# NodeMCU_AC_Switch.net
KiCad netlist of a schematic drawn in EAGLE
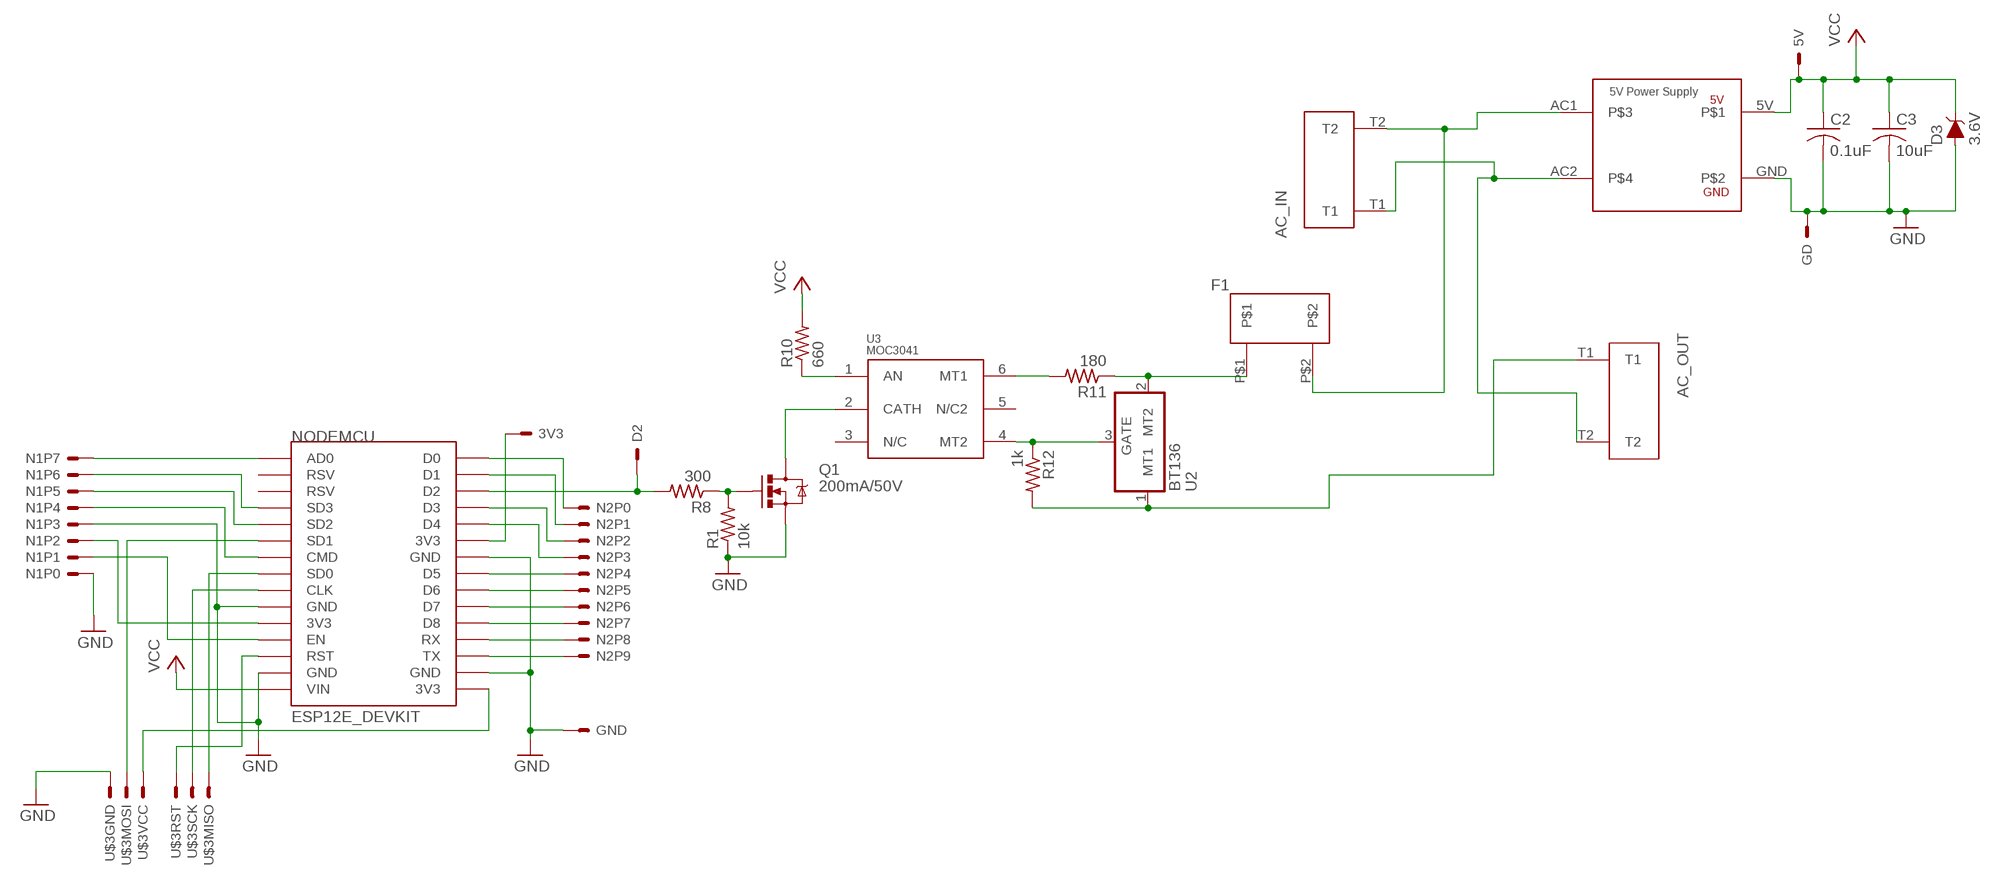
[diagram p0: schematic, sheet 1]

(export (version "E")
  (design (tool "Eeschema 10.0.6"))
  (components
    (comp (ref "3V3")
      (value "1PINHEADER_S")
      (footprint "eagle-import:1PINHEADER_S")
      (libsource (lib "eagle-import") (part "1PINHEADER_S"))
    )
    (comp (ref "5V")
      (value "1PINHEADER_S")
      (footprint "eagle-import:1PINHEADER_S")
      (libsource (lib "eagle-import") (part "1PINHEADER_S"))
    )
    (comp (ref "AC_IN")
      (value "2PIN_SCREW_TERM")
      (footprint "eagle-import:2PIN_SCREW_TERM")
      (libsource (lib "eagle-import") (part "2PIN_SCREW_TERM"))
    )
    (comp (ref "AC_OUT")
      (value "2PIN_SCREW_TERM")
      (footprint "eagle-import:2PIN_SCREW_TERM")
      (libsource (lib "eagle-import") (part "2PIN_SCREW_TERM"))
    )
    (comp (ref "C2")
      (value "0.1uF")
      (footprint "eagle-import:C1206")
      (libsource (lib "eagle-import") (part "C-USC1206"))
    )
    (comp (ref "C3")
      (value "10uF")
      (footprint "eagle-import:C1206")
      (libsource (lib "eagle-import") (part "C-USC1206"))
    )
    (comp (ref "D2")
      (value "1PINHEADER_S")
      (footprint "eagle-import:1PINHEADER_S")
      (libsource (lib "eagle-import") (part "1PINHEADER_S"))
    )
    (comp (ref "D3")
      (value "3.6V")
      (footprint "eagle-import:SOD-323")
      (libsource (lib "eagle-import") (part "DIODE-ZENER-BZT52C3V6S"))
    )
    (comp (ref "F1")
      (value "FUSE_HOLDER")
      (footprint "eagle-import:FUSE_HOLDER")
      (libsource (lib "eagle-import") (part "FUSE_HOLDER"))
    )
    (comp (ref "GD")
      (value "1PINHEADER_S")
      (footprint "eagle-import:1PINHEADER_S")
      (libsource (lib "eagle-import") (part "1PINHEADER_S"))
    )
    (comp (ref "GND")
      (value "1PINHEADER_S")
      (footprint "eagle-import:1PINHEADER_S")
      (libsource (lib "eagle-import") (part "1PINHEADER_S"))
    )
    (comp (ref "N1")
      (value "8PINHEADER")
      (footprint "eagle-import:8PINHEADER")
      (libsource (lib "eagle-import") (part "8PINHEADER"))
    )
    (comp (ref "N2")
      (value "10PINHEADER")
      (footprint "eagle-import:10PINHEADER")
      (libsource (lib "eagle-import") (part "10PINHEADER"))
    )
    (comp (ref "NODEMCU")
      (value "ESP12E_DEVKIT")
      (footprint "eagle-import:ESP12E_DEVKIT")
      (libsource (lib "eagle-import") (part "ESP12E_DEVKIT"))
    )
    (comp (ref "Q1")
      (value "200mA/50V")
      (footprint "eagle-import:SOT23-3")
      (libsource (lib "eagle-import") (part "MOSFET-NCHANNELBSS138"))
    )
    (comp (ref "R1")
      (value "10k")
      (footprint "eagle-import:R1206")
      (libsource (lib "eagle-import") (part "R-US_R1206"))
    )
    (comp (ref "R8")
      (value "300")
      (footprint "eagle-import:R1206")
      (libsource (lib "eagle-import") (part "R-US_R1206"))
    )
    (comp (ref "R10")
      (value "660")
      (footprint "eagle-import:R1206")
      (libsource (lib "eagle-import") (part "R-US_R1206"))
    )
    (comp (ref "R11")
      (value "180")
      (footprint "eagle-import:R1206")
      (libsource (lib "eagle-import") (part "R-US_R1206"))
    )
    (comp (ref "R12")
      (value "1k")
      (footprint "eagle-import:R1206")
      (libsource (lib "eagle-import") (part "R-US_R1206"))
    )
    (comp (ref "U$2")
      (value "5V_POWER_SUPPLY")
      (footprint "eagle-import:5V_POWER_SUPPLY")
      (libsource (lib "eagle-import") (part "5V_POWER_SUPPLY"))
    )
    (comp (ref "U$3")
      (value "2X3_HEADER")
      (footprint "eagle-import:2X3_HEADER")
      (libsource (lib "eagle-import") (part "2X3_HEADER"))
    )
    (comp (ref "U2")
      (value "BT136")
      (footprint "eagle-import:BT136")
      (libsource (lib "eagle-import") (part "BT136"))
    )
    (comp (ref "U3")
      (value "MOC3041")
      (footprint "eagle-import:MOC3041")
      (libsource (lib "eagle-import") (part "MOC3041"))
    )
  )
  (nets
    (net (code "1") (name "GND") (class "Default")
      (node (ref "C2") (pin "2") (pinfunction "2_2") (pintype "passive"))
      (node (ref "C3") (pin "2") (pinfunction "2_2") (pintype "passive"))
      (node (ref "D3") (pin "A") (pinfunction "A_A") (pintype "passive"))
      (node (ref "GD") (pin "P$1") (pinfunction "S_P$1") (pintype "passive"))
      (node (ref "GND") (pin "P$1") (pinfunction "S_P$1") (pintype "passive"))
      (node (ref "N1") (pin "P0") (pinfunction "S_P0") (pintype "passive"))
      (node (ref "N1") (pin "P3") (pinfunction "S_P3") (pintype "passive"))
      (node (ref "NODEMCU") (pin "GND@0") (pinfunction "GND_GND@0") (pintype "bidirectional"))
      (node (ref "NODEMCU") (pin "GND@1") (pinfunction "GND_GND@1") (pintype "bidirectional"))
      (node (ref "NODEMCU") (pin "GND@2") (pinfunction "GND_GND@2") (pintype "bidirectional"))
      (node (ref "NODEMCU") (pin "GND@3") (pinfunction "GND_GND@3") (pintype "bidirectional"))
      (node (ref "Q1") (pin "2") (pinfunction "S_2") (pintype "passive"))
      (node (ref "R1") (pin "1") (pinfunction "1_1") (pintype "passive"))
      (node (ref "U$2") (pin "GND") (pinfunction "P$2_GND") (pintype "bidirectional"))
      (node (ref "U$3") (pin "GND") (pinfunction "S_GND") (pintype "passive"))
    )
    (net (code "2") (name "Net-(3V3-S)") (class "Default")
      (node (ref "3V3") (pin "P$1") (pinfunction "S_P$1") (pintype "passive"))
      (node (ref "NODEMCU") (pin "3V3@1") (pinfunction "3V3_3V3@1") (pintype "bidirectional"))
    )
    (net (code "3") (name "Net-(D2-S)") (class "Default")
      (node (ref "D2") (pin "P$1") (pinfunction "S_P$1") (pintype "passive"))
      (node (ref "NODEMCU") (pin "D2") (pinfunction "D2_D2") (pintype "bidirectional"))
      (node (ref "R8") (pin "2") (pinfunction "2_2") (pintype "passive"))
    )
    (net (code "4") (name "Net-(N1B-S)") (class "Default")
      (node (ref "N1") (pin "P1") (pinfunction "S_P1") (pintype "passive"))
      (node (ref "NODEMCU") (pin "EN") (pinfunction "EN_EN") (pintype "bidirectional"))
    )
    (net (code "5") (name "Net-(N1C-S)") (class "Default")
      (node (ref "N1") (pin "P2") (pinfunction "S_P2") (pintype "passive"))
      (node (ref "NODEMCU") (pin "3V3@0") (pinfunction "3V3_3V3@0") (pintype "bidirectional"))
    )
    (net (code "6") (name "Net-(N1E-S)") (class "Default")
      (node (ref "N1") (pin "P4") (pinfunction "S_P4") (pintype "passive"))
      (node (ref "NODEMCU") (pin "CMD") (pinfunction "CMD_CMD") (pintype "bidirectional"))
    )
    (net (code "7") (name "Net-(N1F-S)") (class "Default")
      (node (ref "N1") (pin "P5") (pinfunction "S_P5") (pintype "passive"))
      (node (ref "NODEMCU") (pin "SD2") (pinfunction "SD2_SD2") (pintype "bidirectional"))
    )
    (net (code "8") (name "Net-(N1G-S)") (class "Default")
      (node (ref "N1") (pin "P6") (pinfunction "S_P6") (pintype "passive"))
      (node (ref "NODEMCU") (pin "SD3") (pinfunction "SD3_SD3") (pintype "bidirectional"))
    )
    (net (code "9") (name "Net-(N1H-S)") (class "Default")
      (node (ref "N1") (pin "P7") (pinfunction "S_P7") (pintype "passive"))
      (node (ref "NODEMCU") (pin "AD0") (pinfunction "AD0_AD0") (pintype "bidirectional"))
    )
    (net (code "10") (name "Net-(N2A-S)") (class "Default")
      (node (ref "N2") (pin "P0") (pinfunction "S_P0") (pintype "passive"))
      (node (ref "NODEMCU") (pin "D0") (pinfunction "D0_D0") (pintype "bidirectional"))
    )
    (net (code "11") (name "Net-(N2B-S)") (class "Default")
      (node (ref "N2") (pin "P1") (pinfunction "S_P1") (pintype "passive"))
      (node (ref "NODEMCU") (pin "D1") (pinfunction "D1_D1") (pintype "bidirectional"))
    )
    (net (code "12") (name "Net-(N2C-S)") (class "Default")
      (node (ref "N2") (pin "P2") (pinfunction "S_P2") (pintype "passive"))
      (node (ref "NODEMCU") (pin "D3") (pinfunction "D3_D3") (pintype "bidirectional"))
    )
    (net (code "13") (name "Net-(N2D-S)") (class "Default")
      (node (ref "N2") (pin "P3") (pinfunction "S_P3") (pintype "passive"))
      (node (ref "NODEMCU") (pin "D4") (pinfunction "D4_D4") (pintype "bidirectional"))
    )
    (net (code "14") (name "Net-(N2E-S)") (class "Default")
      (node (ref "N2") (pin "P4") (pinfunction "S_P4") (pintype "passive"))
      (node (ref "NODEMCU") (pin "D5") (pinfunction "D5_D5") (pintype "bidirectional"))
    )
    (net (code "15") (name "Net-(N2F-S)") (class "Default")
      (node (ref "N2") (pin "P5") (pinfunction "S_P5") (pintype "passive"))
      (node (ref "NODEMCU") (pin "D6") (pinfunction "D6_D6") (pintype "bidirectional"))
    )
    (net (code "16") (name "Net-(N2G-S)") (class "Default")
      (node (ref "N2") (pin "P6") (pinfunction "S_P6") (pintype "passive"))
      (node (ref "NODEMCU") (pin "D7") (pinfunction "D7_D7") (pintype "bidirectional"))
    )
    (net (code "17") (name "Net-(N2H-S)") (class "Default")
      (node (ref "N2") (pin "P7") (pinfunction "S_P7") (pintype "passive"))
      (node (ref "NODEMCU") (pin "D8") (pinfunction "D8_D8") (pintype "bidirectional"))
    )
    (net (code "18") (name "Net-(N2I-S)") (class "Default")
      (node (ref "N2") (pin "P8") (pinfunction "S_P8") (pintype "passive"))
      (node (ref "NODEMCU") (pin "RX") (pinfunction "RX_RX") (pintype "bidirectional"))
    )
    (net (code "19") (name "Net-(N2J-S)") (class "Default")
      (node (ref "N2") (pin "P9") (pinfunction "S_P9") (pintype "passive"))
      (node (ref "NODEMCU") (pin "TX") (pinfunction "TX_TX") (pintype "bidirectional"))
    )
    (net (code "20") (name "Net-(Q1-D)") (class "Default")
      (node (ref "Q1") (pin "3") (pinfunction "D_3") (pintype "passive"))
      (node (ref "U3") (pin "2") (pinfunction "CATH_2") (pintype "bidirectional"))
    )
    (net (code "21") (name "Net-(Q1-G)") (class "Default")
      (node (ref "Q1") (pin "1") (pinfunction "G_1") (pintype "passive"))
      (node (ref "R1") (pin "2") (pinfunction "2_2") (pintype "passive"))
      (node (ref "R8") (pin "1") (pinfunction "1_1") (pintype "passive"))
    )
    (net (code "22") (name "Net-(U$2-P$3)") (class "Default")
      (node (ref "AC_IN") (pin "T2") (pinfunction "T2_T2") (pintype "bidirectional"))
      (node (ref "F1") (pin "P$2") (pinfunction "P$2_P$2") (pintype "bidirectional"))
      (node (ref "U$2") (pin "AC1") (pinfunction "P$3_AC1") (pintype "bidirectional"))
    )
    (net (code "23") (name "Net-(U$2-P$4)") (class "Default")
      (node (ref "AC_IN") (pin "T1") (pinfunction "T1_T1") (pintype "bidirectional"))
      (node (ref "AC_OUT") (pin "T2") (pinfunction "T2_T2") (pintype "bidirectional"))
      (node (ref "U$2") (pin "AC2") (pinfunction "P$4_AC2") (pintype "bidirectional"))
    )
    (net (code "24") (name "Net-(U$3B-S)") (class "Default")
      (node (ref "NODEMCU") (pin "SD0") (pinfunction "SD0_SD0") (pintype "bidirectional"))
      (node (ref "U$3") (pin "MISO") (pinfunction "S_MISO") (pintype "passive"))
    )
    (net (code "25") (name "Net-(U$3C-S)") (class "Default")
      (node (ref "NODEMCU") (pin "SD1") (pinfunction "SD1_SD1") (pintype "bidirectional"))
      (node (ref "U$3") (pin "MOSI") (pinfunction "S_MOSI") (pintype "passive"))
    )
    (net (code "26") (name "Net-(U$3D-S)") (class "Default")
      (node (ref "NODEMCU") (pin "RST") (pinfunction "RST_RST") (pintype "bidirectional"))
      (node (ref "U$3") (pin "RST") (pinfunction "S_RST") (pintype "passive"))
    )
    (net (code "27") (name "Net-(U$3E-S)") (class "Default")
      (node (ref "NODEMCU") (pin "CLK") (pinfunction "CLK_CLK") (pintype "bidirectional"))
      (node (ref "U$3") (pin "SCK") (pinfunction "S_SCK") (pintype "passive"))
    )
    (net (code "28") (name "Net-(U$3F-S)") (class "Default")
      (node (ref "NODEMCU") (pin "3V3@2") (pinfunction "3V3_3V3@2") (pintype "bidirectional"))
      (node (ref "U$3") (pin "VCC") (pinfunction "S_VCC") (pintype "passive"))
    )
    (net (code "29") (name "Net-(U2-GATE)") (class "Default")
      (node (ref "R12") (pin "1") (pinfunction "1_1") (pintype "passive"))
      (node (ref "U2") (pin "3") (pinfunction "GATE_3") (pintype "input"))
      (node (ref "U3") (pin "4") (pinfunction "MT2_4") (pintype "bidirectional"))
    )
    (net (code "30") (name "Net-(U2-MT1)") (class "Default")
      (node (ref "AC_OUT") (pin "T1") (pinfunction "T1_T1") (pintype "bidirectional"))
      (node (ref "R12") (pin "2") (pinfunction "2_2") (pintype "passive"))
      (node (ref "U2") (pin "1") (pinfunction "MT1_1") (pintype "input"))
    )
    (net (code "31") (name "Net-(U2-MT2)") (class "Default")
      (node (ref "F1") (pin "P$1") (pinfunction "P$1_P$1") (pintype "bidirectional"))
      (node (ref "R11") (pin "1") (pinfunction "1_1") (pintype "passive"))
      (node (ref "U2") (pin "2") (pinfunction "MT2_2") (pintype "passive"))
    )
    (net (code "32") (name "Net-(U3-AN)") (class "Default")
      (node (ref "R10") (pin "1") (pinfunction "1_1") (pintype "passive"))
      (node (ref "U3") (pin "1") (pinfunction "AN_1") (pintype "bidirectional"))
    )
    (net (code "33") (name "Net-(U3-MT1)") (class "Default")
      (node (ref "R11") (pin "2") (pinfunction "2_2") (pintype "passive"))
      (node (ref "U3") (pin "6") (pinfunction "MT1_6") (pintype "bidirectional"))
    )
    (net (code "34") (name "VCC") (class "Default")
      (node (ref "5V") (pin "P$1") (pinfunction "S_P$1") (pintype "passive"))
      (node (ref "C2") (pin "1") (pinfunction "1_1") (pintype "passive"))
      (node (ref "C3") (pin "1") (pinfunction "1_1") (pintype "passive"))
      (node (ref "D3") (pin "C") (pinfunction "C_C") (pintype "passive"))
      (node (ref "NODEMCU") (pin "VIN") (pinfunction "VIN_VIN") (pintype "bidirectional"))
      (node (ref "R10") (pin "2") (pinfunction "2_2") (pintype "passive"))
      (node (ref "U$2") (pin "5V") (pinfunction "P$1_5V") (pintype "bidirectional"))
    )
    (net (code "35") (name "unconnected-(NODEMCU-RSV-PadRSV@0)") (class "Default")
      (node (ref "NODEMCU") (pin "RSV@0") (pinfunction "RSV_RSV@0") (pintype "bidirectional"))
    )
    (net (code "36") (name "unconnected-(NODEMCU-RSV-PadRSV@1)") (class "Default")
      (node (ref "NODEMCU") (pin "RSV@1") (pinfunction "RSV_RSV@1") (pintype "bidirectional"))
    )
    (net (code "37") (name "unconnected-(U3-N{slash}C-Pad3)") (class "Default")
      (node (ref "U3") (pin "3") (pinfunction "N/C_3") (pintype "bidirectional"))
    )
    (net (code "38") (name "unconnected-(U3-N{slash}C2-Pad5)") (class "Default")
      (node (ref "U3") (pin "5") (pinfunction "N/C2_5") (pintype "bidirectional"))
    )
  )
)
